# proton_pack_neopixel_driver.net
KiCad netlist of a schematic drawn in EAGLE
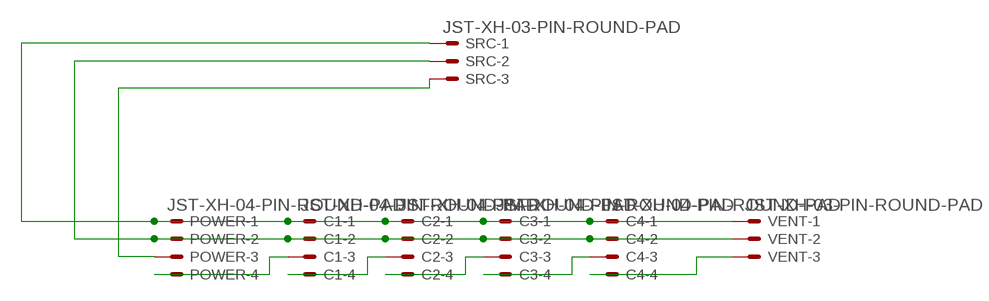
[diagram p0: schematic, sheet 1]

(export (version "E")
  (design (tool "Eeschema 10.0.6"))
  (components
    (comp (ref "C1")
      (value "JST-XH-04-PIN-ROUND-PAD")
      (footprint "eagle-import:JST-XH-04-PACKAGE-ROUND-PAD")
      (libsource (lib "eagle-import") (part "JST-XH-04-PIN-ROUND-PAD"))
    )
    (comp (ref "C2")
      (value "JST-XH-04-PIN-ROUND-PAD")
      (footprint "eagle-import:JST-XH-04-PACKAGE-ROUND-PAD")
      (libsource (lib "eagle-import") (part "JST-XH-04-PIN-ROUND-PAD"))
    )
    (comp (ref "C3")
      (value "JST-XH-04-PIN-ROUND-PAD")
      (footprint "eagle-import:JST-XH-04-PACKAGE-ROUND-PAD")
      (libsource (lib "eagle-import") (part "JST-XH-04-PIN-ROUND-PAD"))
    )
    (comp (ref "C4")
      (value "JST-XH-04-PIN-ROUND-PAD")
      (footprint "eagle-import:JST-XH-04-PACKAGE-ROUND-PAD")
      (libsource (lib "eagle-import") (part "JST-XH-04-PIN-ROUND-PAD"))
    )
    (comp (ref "POWER")
      (value "JST-XH-04-PIN-ROUND-PAD")
      (footprint "eagle-import:JST-XH-04-PACKAGE-ROUND-PAD")
      (libsource (lib "eagle-import") (part "JST-XH-04-PIN-ROUND-PAD"))
    )
    (comp (ref "SRC")
      (value "JST-XH-03-PIN-ROUND-PAD")
      (footprint "eagle-import:JST-XH-03-PACKAGE-ROUND-PAD")
      (libsource (lib "eagle-import") (part "JST-XH-03-PIN-ROUND-PAD"))
    )
    (comp (ref "VENT")
      (value "JST-XH-03-PIN-ROUND-PAD")
      (footprint "eagle-import:JST-XH-03-PACKAGE-ROUND-PAD")
      (libsource (lib "eagle-import") (part "JST-XH-03-PIN-ROUND-PAD"))
    )
  )
  (nets
    (net (code "1") (name "Net-(C1A-S)") (class "Default")
      (node (ref "C1") (pin "1") (pinfunction "S_1") (pintype "passive"))
      (node (ref "C2") (pin "1") (pinfunction "S_1") (pintype "passive"))
      (node (ref "C3") (pin "1") (pinfunction "S_1") (pintype "passive"))
      (node (ref "C4") (pin "1") (pinfunction "S_1") (pintype "passive"))
      (node (ref "POWER") (pin "1") (pinfunction "S_1") (pintype "passive"))
      (node (ref "SRC") (pin "1") (pinfunction "S_1") (pintype "passive"))
      (node (ref "VENT") (pin "1") (pinfunction "S_1") (pintype "passive"))
    )
    (net (code "2") (name "Net-(C1B-S)") (class "Default")
      (node (ref "C1") (pin "2") (pinfunction "S_2") (pintype "passive"))
      (node (ref "C2") (pin "2") (pinfunction "S_2") (pintype "passive"))
      (node (ref "C3") (pin "2") (pinfunction "S_2") (pintype "passive"))
      (node (ref "C4") (pin "2") (pinfunction "S_2") (pintype "passive"))
      (node (ref "POWER") (pin "2") (pinfunction "S_2") (pintype "passive"))
      (node (ref "SRC") (pin "2") (pinfunction "S_2") (pintype "passive"))
      (node (ref "VENT") (pin "2") (pinfunction "S_2") (pintype "passive"))
    )
    (net (code "3") (name "Net-(C1C-S)") (class "Default")
      (node (ref "C1") (pin "3") (pinfunction "S_3") (pintype "passive"))
      (node (ref "POWER") (pin "4") (pinfunction "S_4") (pintype "passive"))
    )
    (net (code "4") (name "Net-(C1D-S)") (class "Default")
      (node (ref "C1") (pin "4") (pinfunction "S_4") (pintype "passive"))
      (node (ref "C2") (pin "3") (pinfunction "S_3") (pintype "passive"))
    )
    (net (code "5") (name "Net-(C2D-S)") (class "Default")
      (node (ref "C2") (pin "4") (pinfunction "S_4") (pintype "passive"))
      (node (ref "C3") (pin "3") (pinfunction "S_3") (pintype "passive"))
    )
    (net (code "6") (name "Net-(C3D-S)") (class "Default")
      (node (ref "C3") (pin "4") (pinfunction "S_4") (pintype "passive"))
      (node (ref "C4") (pin "3") (pinfunction "S_3") (pintype "passive"))
    )
    (net (code "7") (name "Net-(C4D-S)") (class "Default")
      (node (ref "C4") (pin "4") (pinfunction "S_4") (pintype "passive"))
      (node (ref "VENT") (pin "3") (pinfunction "S_3") (pintype "passive"))
    )
    (net (code "8") (name "Net-(POWERC-S)") (class "Default")
      (node (ref "POWER") (pin "3") (pinfunction "S_3") (pintype "passive"))
      (node (ref "SRC") (pin "3") (pinfunction "S_3") (pintype "passive"))
    )
  )
)
